# SparkFun_Soil_Moisture_Sensor.net
KiCad netlist of a schematic drawn in EAGLE
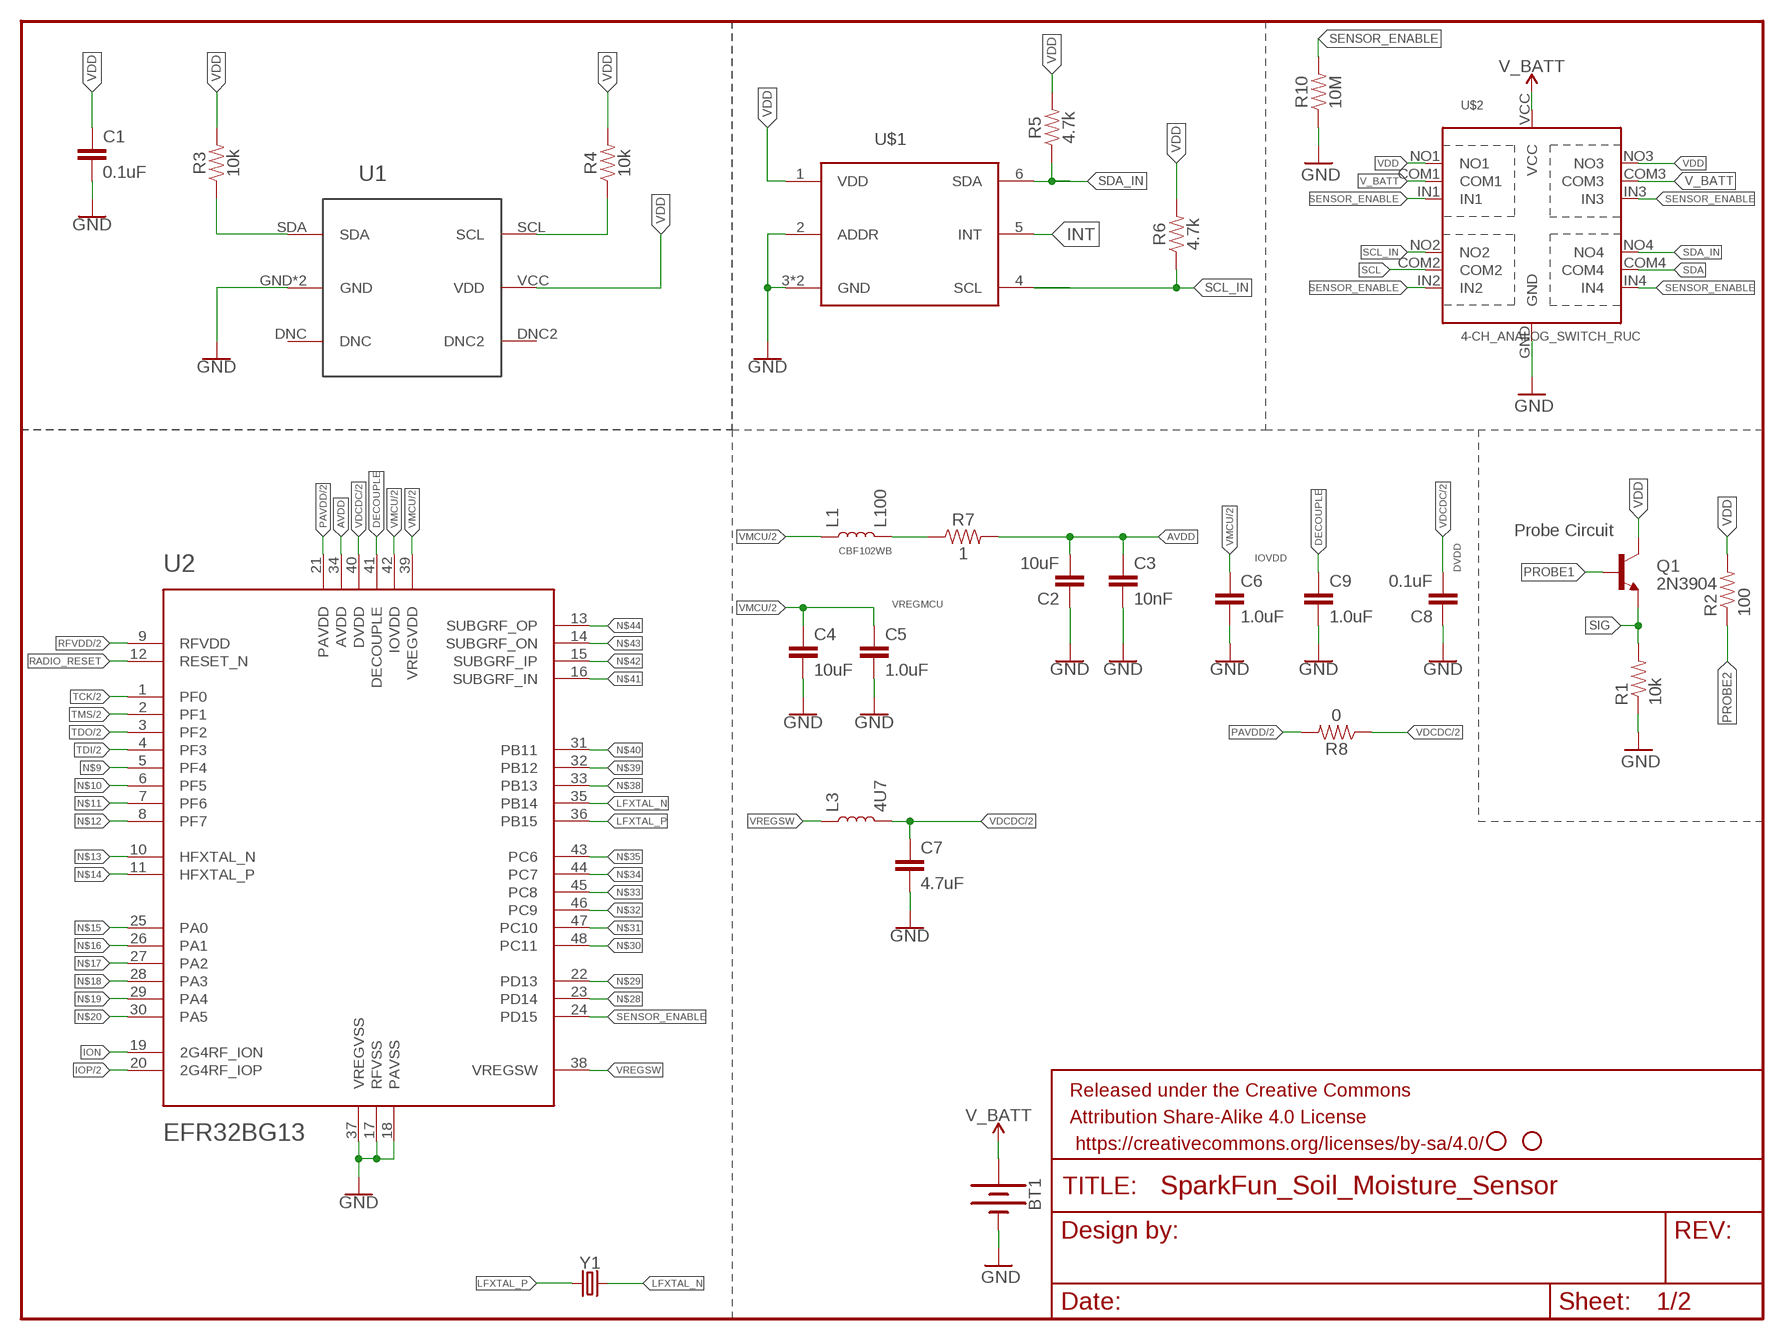
[diagram p0: schematic, sheet 1]
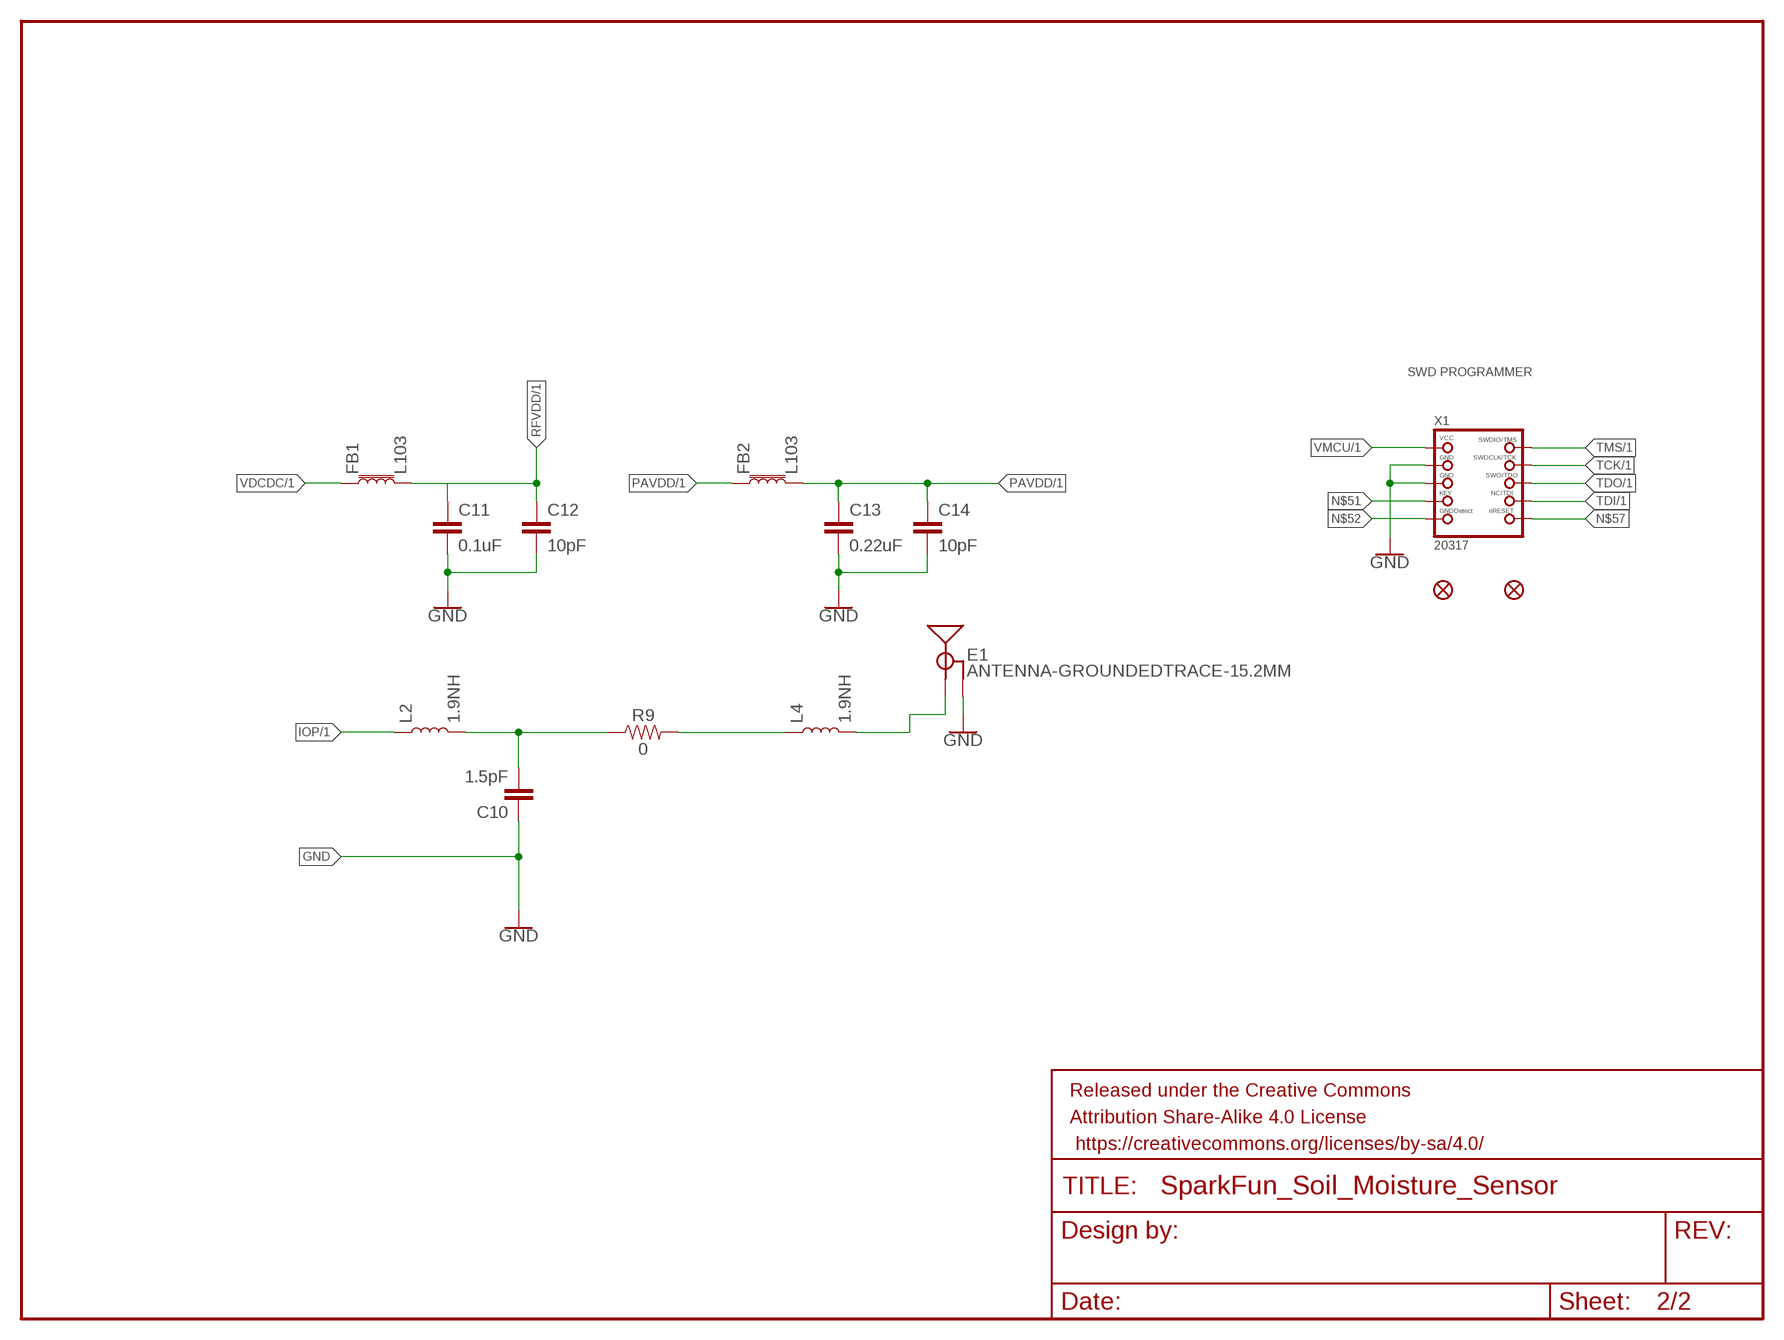
[diagram p1: schematic, sheet 2]

(export (version "E")
  (design (tool "Eeschema 10.0.6"))
  (components
    (comp (ref "BT1")
      (value "BATTERY-20MM_SMD_4LEGS_OVERPASTE")
      (footprint "eagle-import:BATTCON_20MM_4LEGS_OVERPASTE")
      (libsource (lib "eagle-import") (part "BATTERY-20MM_SMD_4LEGS_OVERPASTE"))
    )
    (comp (ref "C1")
      (value "0.1uF")
      (footprint "eagle-import:0603")
      (libsource (lib "eagle-import") (part "0.1UF-0603-25V-(+80/-20%)"))
    )
    (comp (ref "C2")
      (value "10uF")
      (footprint "eagle-import:0603")
      (libsource (lib "eagle-import") (part "10UF-0603-6.3V-20%"))
    )
    (comp (ref "C3")
      (value "10nF")
      (footprint "eagle-import:0603")
      (libsource (lib "eagle-import") (part "10NF-0603-50V-10%"))
    )
    (comp (ref "C4")
      (value "10uF")
      (footprint "eagle-import:0603")
      (libsource (lib "eagle-import") (part "10UF-0603-6.3V-20%"))
    )
    (comp (ref "C5")
      (value "1.0uF")
      (footprint "eagle-import:0603")
      (libsource (lib "eagle-import") (part "1.0UF-0603-16V-10%"))
    )
    (comp (ref "C6")
      (value "1.0uF")
      (footprint "eagle-import:0603")
      (libsource (lib "eagle-import") (part "1.0UF-0603-16V-10%"))
    )
    (comp (ref "C7")
      (value "4.7uF")
      (footprint "eagle-import:0603")
      (libsource (lib "eagle-import") (part "4.7UF0603"))
    )
    (comp (ref "C8")
      (value "0.1uF")
      (footprint "eagle-import:0603")
      (libsource (lib "eagle-import") (part "0.1UF-0603-25V-(+80/-20%)"))
    )
    (comp (ref "C9")
      (value "1.0uF")
      (footprint "eagle-import:0603")
      (libsource (lib "eagle-import") (part "1.0UF-0603-16V-10%"))
    )
    (comp (ref "FRAME1")
      (value "FRAME-LETTER")
      (footprint "eagle-import:CREATIVE_COMMONS")
      (libsource (lib "eagle-import") (part "FRAME-LETTER"))
    )
    (comp (ref "L1")
      (value "L100")
      (footprint "eagle-import:0603")
      (libsource (lib "eagle-import") (part "INDUCTOR-0603-33NH"))
    )
    (comp (ref "L3")
      (value "4U7")
      (footprint "eagle-import:1212(3030METRIC)")
      (libsource (lib "eagle-import") (part "4U7"))
    )
    (comp (ref "Q1")
      (value "2N3904")
      (footprint "eagle-import:SOT23-3")
      (libsource (lib "eagle-import") (part "TRANSISTOR_NPNMMBT2222A"))
    )
    (comp (ref "R1")
      (value "10k")
      (footprint "eagle-import:0603-RES")
      (libsource (lib "eagle-import") (part "100OHM-1/4W-5%(0603)"))
    )
    (comp (ref "R2")
      (value "100")
      (footprint "eagle-import:0603-RES")
      (libsource (lib "eagle-import") (part "100OHM-1/4W-5%(0603)"))
    )
    (comp (ref "R3")
      (value "10k")
      (footprint "eagle-import:0603")
      (libsource (lib "eagle-import") (part "10KOHM-0603-1/10W-1%"))
    )
    (comp (ref "R4")
      (value "10k")
      (footprint "eagle-import:0603")
      (libsource (lib "eagle-import") (part "10KOHM-0603-1/10W-1%"))
    )
    (comp (ref "R5")
      (value "4.7k")
      (footprint "eagle-import:0603")
      (libsource (lib "eagle-import") (part "4.7KOHM-0603-1/10W-1%"))
    )
    (comp (ref "R6")
      (value "4.7k")
      (footprint "eagle-import:0603")
      (libsource (lib "eagle-import") (part "4.7KOHM-0603-1/10W-1%"))
    )
    (comp (ref "R7")
      (value "1")
      (footprint "eagle-import:0603")
      (libsource (lib "eagle-import") (part "1OHM-0603-1/10W-1%"))
    )
    (comp (ref "R8")
      (value "0")
      (footprint "eagle-import:0603")
      (libsource (lib "eagle-import") (part "0OHM-0603-1/10W-5%"))
    )
    (comp (ref "R10")
      (value "10M")
      (footprint "eagle-import:0603")
      (libsource (lib "eagle-import") (part "10MOHM-0603-1/10W-5%"))
    )
    (comp (ref "STANDOFF1")
      (value "STAND-OFF")
      (footprint "eagle-import:STAND-OFF")
      (libsource (lib "eagle-import") (part "STAND-OFF"))
    )
    (comp (ref "STANDOFF2")
      (value "STAND-OFF")
      (footprint "eagle-import:STAND-OFF")
      (libsource (lib "eagle-import") (part "STAND-OFF"))
    )
    (comp (ref "U$1")
      (value "OPT3001DNPT")
      (footprint "eagle-import:6PIN_USON")
      (libsource (lib "eagle-import") (part "OPT3001DNPT"))
    )
    (comp (ref "U$2")
      (value "4-CH_ANALOG_SWITCH_RUC")
      (footprint "eagle-import:PX2QFN14_RUC")
      (libsource (lib "eagle-import") (part "4-CH_ANALOG_SWITCH_RUC"))
    )
    (comp (ref "U1")
      (value "SI7021_TEMP_HUMIDTY")
      (footprint "eagle-import:DFN-6")
      (libsource (lib "eagle-import") (part "SI7021_TEMP_HUMIDTY"))
    )
    (comp (ref "U2")
      (value "EFR32BG13")
      (footprint "eagle-import:QFN48")
      (libsource (lib "eagle-import") (part "EFR32BG13"))
    )
    (comp (ref "Y1")
      (value "32.768KHZ_LOW_FREQ_CRYSTAL")
      (footprint "eagle-import:CRYSTAL_1.2X0.6")
      (libsource (lib "eagle-import") (part "32.768KHZ_LOW_FREQ_CRYSTAL"))
    )
    (comp (ref "C10")
      (value "1.5pF")
      (footprint "eagle-import:0603")
      (libsource (lib "eagle-import") (part "1.5PF-0603-50V-16.667%"))
    )
    (comp (ref "C11")
      (value "0.1uF")
      (footprint "eagle-import:0603")
      (libsource (lib "eagle-import") (part "0.1UF-0603-25V-(+80/-20%)"))
    )
    (comp (ref "C12")
      (value "10pF")
      (footprint "eagle-import:0603")
      (libsource (lib "eagle-import") (part "10PF-0603-50V-5%"))
    )
    (comp (ref "C13")
      (value "0.22uF")
      (footprint "eagle-import:0603")
      (libsource (lib "eagle-import") (part "0.22UF-0603-25V-10%"))
    )
    (comp (ref "C14")
      (value "10pF")
      (footprint "eagle-import:0603")
      (libsource (lib "eagle-import") (part "10PF-0603-50V-5%"))
    )
    (comp (ref "E1")
      (value "ANTENNA-GROUNDEDTRACE-15.2MM")
      (footprint "eagle-import:TRACE_ANTENNA_2.4GHZ_15.2MM")
      (libsource (lib "eagle-import") (part "ANTENNA-GROUNDEDTRACE-15.2MM"))
    )
    (comp (ref "FB1")
      (value "L103")
      (footprint "eagle-import:0603")
      (libsource (lib "eagle-import") (part "FERRITE_BEAD-0603"))
    )
    (comp (ref "FB2")
      (value "L103")
      (footprint "eagle-import:0603")
      (libsource (lib "eagle-import") (part "FERRITE_BEAD-0603"))
    )
    (comp (ref "FID1")
      (value "FIDUCIAL\"\"")
      (footprint "eagle-import:FIDUCIAL_1MM")
      (libsource (lib "eagle-import") (part "FIDUCIAL{dblquote}{dblquote}"))
    )
    (comp (ref "FID2")
      (value "FIDUCIAL\"\"")
      (footprint "eagle-import:FIDUCIAL_1MM")
      (libsource (lib "eagle-import") (part "FIDUCIAL{dblquote}{dblquote}"))
    )
    (comp (ref "FRAME2")
      (value "FRAME-LETTER")
      (footprint "eagle-import:CREATIVE_COMMONS")
      (libsource (lib "eagle-import") (part "FRAME-LETTER"))
    )
    (comp (ref "L2")
      (value "1.9NH")
      (footprint "eagle-import:0402")
      (libsource (lib "eagle-import") (part "INDUCTOR-0402-3.9NH"))
    )
    (comp (ref "L4")
      (value "1.9NH")
      (footprint "eagle-import:0402")
      (libsource (lib "eagle-import") (part "INDUCTOR-0402-3.9NH"))
    )
    (comp (ref "R9")
      (value "0")
      (footprint "eagle-import:0805")
      (libsource (lib "eagle-import") (part "0.22OHM-0805-1/4W-1%"))
    )
    (comp (ref "X1")
      (value "20317")
      (footprint "eagle-import:2X05_1.27MM_BOX_POSTS")
      (libsource (lib "eagle-import") (part "JTAG-CORTEXBOXPOSTS"))
    )
  )
  (nets
    (net (code "1") (name "AVDD") (class "Default")
      (node (ref "C2") (pin "2") (pinfunction "2_2") (pintype "passive"))
      (node (ref "C3") (pin "1") (pinfunction "1_1") (pintype "passive"))
      (node (ref "R7") (pin "2") (pinfunction "2_2") (pintype "passive"))
      (node (ref "U2") (pin "34") (pinfunction "AVDD_34") (pintype "bidirectional"))
    )
    (net (code "2") (name "DECOUPLE") (class "Default")
      (node (ref "C9") (pin "1") (pinfunction "1_1") (pintype "passive"))
      (node (ref "U2") (pin "41") (pinfunction "DECOUPLE_41") (pintype "bidirectional"))
    )
    (net (code "3") (name "GND") (class "Default")
      (node (ref "BT1") (pin "2") (pinfunction "-_2") (pintype "power_in"))
      (node (ref "C1") (pin "2") (pinfunction "2_2") (pintype "passive"))
      (node (ref "C10") (pin "1") (pinfunction "1_1") (pintype "passive"))
      (node (ref "C11") (pin "2") (pinfunction "2_2") (pintype "passive"))
      (node (ref "C12") (pin "2") (pinfunction "2_2") (pintype "passive"))
      (node (ref "C13") (pin "2") (pinfunction "2_2") (pintype "passive"))
      (node (ref "C14") (pin "2") (pinfunction "2_2") (pintype "passive"))
      (node (ref "C2") (pin "1") (pinfunction "1_1") (pintype "passive"))
      (node (ref "C3") (pin "2") (pinfunction "2_2") (pintype "passive"))
      (node (ref "C4") (pin "2") (pinfunction "2_2") (pintype "passive"))
      (node (ref "C5") (pin "2") (pinfunction "2_2") (pintype "passive"))
      (node (ref "C6") (pin "2") (pinfunction "2_2") (pintype "passive"))
      (node (ref "C7") (pin "2") (pinfunction "2_2") (pintype "passive"))
      (node (ref "C8") (pin "1") (pinfunction "1_1") (pintype "passive"))
      (node (ref "C9") (pin "2") (pinfunction "2_2") (pintype "passive"))
      (node (ref "E1") (pin "GND") (pinfunction "GND_GND") (pintype "bidirectional"))
      (node (ref "R1") (pin "1") (pinfunction "1_1") (pintype "passive"))
      (node (ref "R10") (pin "1") (pinfunction "1_1") (pintype "passive"))
      (node (ref "U$1") (pin "2") (pinfunction "ADDR_2") (pintype "bidirectional"))
      (node (ref "U$1") (pin "3") (pinfunction "GND_3") (pintype "bidirectional"))
      (node (ref "U$1") (pin "GND") (pinfunction "GND_GND") (pintype "bidirectional"))
      (node (ref "U$2") (pin "GND") (pinfunction "GND_GND") (pintype "bidirectional"))
      (node (ref "U1") (pin "GND") (pinfunction "GND_GND") (pintype "bidirectional"))
      (node (ref "U1") (pin "GND2") (pinfunction "GND_GND2") (pintype "bidirectional"))
      (node (ref "U2") (pin "17") (pinfunction "RFVSS_17") (pintype "bidirectional"))
      (node (ref "U2") (pin "18") (pinfunction "PAVSS_18") (pintype "bidirectional"))
      (node (ref "U2") (pin "37") (pinfunction "VREGVSS_37") (pintype "bidirectional"))
      (node (ref "X1") (pin "3") (pinfunction "GND_3") (pintype "power_in"))
      (node (ref "X1") (pin "5") (pinfunction "GND_5") (pintype "power_in"))
    )
    (net (code "4") (name "INT") (class "Default")
      (node (ref "U$1") (pin "5") (pinfunction "INT_5") (pintype "bidirectional"))
    )
    (net (code "5") (name "ION") (class "Default")
      (node (ref "U2") (pin "19") (pinfunction "2G4RF_ION_19") (pintype "bidirectional"))
    )
    (net (code "6") (name "IOP") (class "Default")
      (node (ref "L2") (pin "1") (pinfunction "1_1") (pintype "passive"))
      (node (ref "U2") (pin "20") (pinfunction "2G4RF_IOP_20") (pintype "bidirectional"))
    )
    (net (code "7") (name "LFXTAL_N") (class "Default")
      (node (ref "U2") (pin "35") (pinfunction "PB14_35") (pintype "bidirectional"))
      (node (ref "Y1") (pin "P$2") (pinfunction "2_P$2") (pintype "passive"))
    )
    (net (code "8") (name "LFXTAL_P") (class "Default")
      (node (ref "U2") (pin "36") (pinfunction "PB15_36") (pintype "bidirectional"))
      (node (ref "Y1") (pin "P$1") (pinfunction "1_P$1") (pintype "passive"))
    )
    (net (code "9") (name "N$9") (class "Default")
      (node (ref "U2") (pin "5") (pinfunction "PF4_5") (pintype "bidirectional"))
    )
    (net (code "10") (name "N$10") (class "Default")
      (node (ref "U2") (pin "6") (pinfunction "PF5_6") (pintype "bidirectional"))
    )
    (net (code "11") (name "N$11") (class "Default")
      (node (ref "U2") (pin "7") (pinfunction "PF6_7") (pintype "bidirectional"))
    )
    (net (code "12") (name "N$12") (class "Default")
      (node (ref "U2") (pin "8") (pinfunction "PF7_8") (pintype "bidirectional"))
    )
    (net (code "13") (name "N$13") (class "Default")
      (node (ref "U2") (pin "10") (pinfunction "HFXTAL_N_10") (pintype "bidirectional"))
    )
    (net (code "14") (name "N$14") (class "Default")
      (node (ref "U2") (pin "11") (pinfunction "HFXTAL_P_11") (pintype "bidirectional"))
    )
    (net (code "15") (name "N$15") (class "Default")
      (node (ref "U2") (pin "25") (pinfunction "PA0_25") (pintype "bidirectional"))
    )
    (net (code "16") (name "N$16") (class "Default")
      (node (ref "U2") (pin "26") (pinfunction "PA1_26") (pintype "bidirectional"))
    )
    (net (code "17") (name "N$17") (class "Default")
      (node (ref "U2") (pin "27") (pinfunction "PA2_27") (pintype "bidirectional"))
    )
    (net (code "18") (name "N$18") (class "Default")
      (node (ref "U2") (pin "28") (pinfunction "PA3_28") (pintype "bidirectional"))
    )
    (net (code "19") (name "N$19") (class "Default")
      (node (ref "U2") (pin "29") (pinfunction "PA4_29") (pintype "bidirectional"))
    )
    (net (code "20") (name "N$20") (class "Default")
      (node (ref "U2") (pin "30") (pinfunction "PA5_30") (pintype "bidirectional"))
    )
    (net (code "21") (name "N$28") (class "Default")
      (node (ref "U2") (pin "23") (pinfunction "PD14_23") (pintype "bidirectional"))
    )
    (net (code "22") (name "N$29") (class "Default")
      (node (ref "U2") (pin "22") (pinfunction "PD13_22") (pintype "bidirectional"))
    )
    (net (code "23") (name "N$30") (class "Default")
      (node (ref "U2") (pin "48") (pinfunction "PC11_48") (pintype "bidirectional"))
    )
    (net (code "24") (name "N$31") (class "Default")
      (node (ref "U2") (pin "47") (pinfunction "PC10_47") (pintype "bidirectional"))
    )
    (net (code "25") (name "N$32") (class "Default")
      (node (ref "U2") (pin "46") (pinfunction "PC9_46") (pintype "bidirectional"))
    )
    (net (code "26") (name "N$33") (class "Default")
      (node (ref "U2") (pin "45") (pinfunction "PC8_45") (pintype "bidirectional"))
    )
    (net (code "27") (name "N$34") (class "Default")
      (node (ref "U2") (pin "44") (pinfunction "PC7_44") (pintype "bidirectional"))
    )
    (net (code "28") (name "N$35") (class "Default")
      (node (ref "U2") (pin "43") (pinfunction "PC6_43") (pintype "bidirectional"))
    )
    (net (code "29") (name "N$38") (class "Default")
      (node (ref "U2") (pin "33") (pinfunction "PB13_33") (pintype "bidirectional"))
    )
    (net (code "30") (name "N$39") (class "Default")
      (node (ref "U2") (pin "32") (pinfunction "PB12_32") (pintype "bidirectional"))
    )
    (net (code "31") (name "N$40") (class "Default")
      (node (ref "U2") (pin "31") (pinfunction "PB11_31") (pintype "bidirectional"))
    )
    (net (code "32") (name "N$41") (class "Default")
      (node (ref "U2") (pin "16") (pinfunction "SUBGRF_IN_16") (pintype "bidirectional"))
    )
    (net (code "33") (name "N$42") (class "Default")
      (node (ref "U2") (pin "15") (pinfunction "SUBGRF_IP_15") (pintype "bidirectional"))
    )
    (net (code "34") (name "N$43") (class "Default")
      (node (ref "U2") (pin "14") (pinfunction "SUBGRF_ON_14") (pintype "bidirectional"))
    )
    (net (code "35") (name "N$44") (class "Default")
      (node (ref "U2") (pin "13") (pinfunction "SUBGRF_OP_13") (pintype "bidirectional"))
    )
    (net (code "36") (name "N$51") (class "Default")
      (node (ref "X1") (pin "7") (pinfunction "KEY_7") (pintype "bidirectional"))
    )
    (net (code "37") (name "N$52") (class "Default")
      (node (ref "X1") (pin "9") (pinfunction "GNDDETECT_9") (pintype "bidirectional"))
    )
    (net (code "38") (name "N$57") (class "Default")
      (node (ref "X1") (pin "10") (pinfunction "NRESET_10") (pintype "bidirectional"))
    )
    (net (code "39") (name "Net-(C10-Pad2)") (class "Default")
      (node (ref "C10") (pin "2") (pinfunction "2_2") (pintype "passive"))
      (node (ref "L2") (pin "2") (pinfunction "2_2") (pintype "passive"))
      (node (ref "R9") (pin "1") (pinfunction "1_1") (pintype "passive"))
    )
    (net (code "40") (name "Net-(E1-SIGNAL)") (class "Default")
      (node (ref "E1") (pin "ANT") (pinfunction "SIGNAL_ANT") (pintype "bidirectional"))
      (node (ref "L4") (pin "2") (pinfunction "2_2") (pintype "passive"))
    )
    (net (code "41") (name "Net-(L1-Pad2)") (class "Default")
      (node (ref "L1") (pin "2") (pinfunction "2_2") (pintype "passive"))
      (node (ref "R7") (pin "1") (pinfunction "1_1") (pintype "passive"))
    )
    (net (code "42") (name "Net-(L4-Pad1)") (class "Default")
      (node (ref "L4") (pin "1") (pinfunction "1_1") (pintype "passive"))
      (node (ref "R9") (pin "2") (pinfunction "2_2") (pintype "passive"))
    )
    (net (code "43") (name "Net-(R3-Pad1)") (class "Default")
      (node (ref "R3") (pin "1") (pinfunction "1_1") (pintype "passive"))
      (node (ref "U1") (pin "SDA") (pinfunction "SDA_SDA") (pintype "bidirectional"))
    )
    (net (code "44") (name "Net-(R4-Pad1)") (class "Default")
      (node (ref "R4") (pin "1") (pinfunction "1_1") (pintype "passive"))
      (node (ref "U1") (pin "SCL") (pinfunction "SCL_SCL") (pintype "bidirectional"))
    )
    (net (code "45") (name "PAVDD") (class "Default")
      (node (ref "C13") (pin "1") (pinfunction "1_1") (pintype "passive"))
      (node (ref "C14") (pin "1") (pinfunction "1_1") (pintype "passive"))
      (node (ref "FB2") (pin "1") (pinfunction "1_1") (pintype "passive"))
      (node (ref "FB2") (pin "2") (pinfunction "2_2") (pintype "passive"))
      (node (ref "R8") (pin "2") (pinfunction "2_2") (pintype "passive"))
      (node (ref "U2") (pin "21") (pinfunction "PAVDD_21") (pintype "bidirectional"))
    )
    (net (code "46") (name "PROBE1") (class "Default")
      (node (ref "Q1") (pin "1") (pinfunction "B_1") (pintype "passive"))
    )
    (net (code "47") (name "PROBE2") (class "Default")
      (node (ref "R2") (pin "1") (pinfunction "1_1") (pintype "passive"))
    )
    (net (code "48") (name "RADIO_RESET") (class "Default")
      (node (ref "U2") (pin "12") (pinfunction "RESET_N_12") (pintype "bidirectional"))
    )
    (net (code "49") (name "RFVDD") (class "Default")
      (node (ref "C11") (pin "1") (pinfunction "1_1") (pintype "passive"))
      (node (ref "C12") (pin "1") (pinfunction "1_1") (pintype "passive"))
      (node (ref "FB1") (pin "2") (pinfunction "2_2") (pintype "passive"))
      (node (ref "U2") (pin "9") (pinfunction "RFVDD_9") (pintype "bidirectional"))
    )
    (net (code "50") (name "SCL") (class "Default")
      (node (ref "U$2") (pin "COM2") (pinfunction "COM2_COM2") (pintype "bidirectional"))
    )
    (net (code "51") (name "SCL_IN") (class "Default")
      (node (ref "R6") (pin "1") (pinfunction "1_1") (pintype "passive"))
      (node (ref "U$1") (pin "4") (pinfunction "SCL_4") (pintype "bidirectional"))
      (node (ref "U$2") (pin "NO2") (pinfunction "NO2_NO2") (pintype "bidirectional"))
    )
    (net (code "52") (name "SDA") (class "Default")
      (node (ref "U$2") (pin "COM4") (pinfunction "COM4_COM4") (pintype "bidirectional"))
    )
    (net (code "53") (name "SDA_IN") (class "Default")
      (node (ref "R5") (pin "1") (pinfunction "1_1") (pintype "passive"))
      (node (ref "U$1") (pin "6") (pinfunction "SDA_6") (pintype "bidirectional"))
      (node (ref "U$2") (pin "NO4") (pinfunction "NO4_NO4") (pintype "bidirectional"))
    )
    (net (code "54") (name "SENSOR_ENABLE") (class "Default")
      (node (ref "R10") (pin "2") (pinfunction "2_2") (pintype "passive"))
      (node (ref "U$2") (pin "IN1") (pinfunction "IN1_IN1") (pintype "bidirectional"))
      (node (ref "U$2") (pin "IN2") (pinfunction "IN2_IN2") (pintype "bidirectional"))
      (node (ref "U$2") (pin "IN3") (pinfunction "IN3_IN3") (pintype "bidirectional"))
      (node (ref "U$2") (pin "IN4") (pinfunction "IN4_IN4") (pintype "bidirectional"))
      (node (ref "U2") (pin "24") (pinfunction "PD15_24") (pintype "bidirectional"))
    )
    (net (code "55") (name "SIG") (class "Default")
      (node (ref "Q1") (pin "2") (pinfunction "E_2") (pintype "passive"))
      (node (ref "R1") (pin "2") (pinfunction "2_2") (pintype "passive"))
    )
    (net (code "56") (name "TCK") (class "Default")
      (node (ref "U2") (pin "1") (pinfunction "PF0_1") (pintype "bidirectional"))
      (node (ref "X1") (pin "4") (pinfunction "SWDCLK_4") (pintype "bidirectional"))
    )
    (net (code "57") (name "TDI") (class "Default")
      (node (ref "U2") (pin "4") (pinfunction "PF3_4") (pintype "bidirectional"))
      (node (ref "X1") (pin "8") (pinfunction "TDI_8") (pintype "bidirectional"))
    )
    (net (code "58") (name "TDO") (class "Default")
      (node (ref "U2") (pin "3") (pinfunction "PF2_3") (pintype "bidirectional"))
      (node (ref "X1") (pin "6") (pinfunction "SWO_6") (pintype "bidirectional"))
    )
    (net (code "59") (name "TMS") (class "Default")
      (node (ref "U2") (pin "2") (pinfunction "PF1_2") (pintype "bidirectional"))
      (node (ref "X1") (pin "2") (pinfunction "SWDIO_2") (pintype "bidirectional"))
    )
    (net (code "60") (name "VDCDC") (class "Default")
      (node (ref "C7") (pin "1") (pinfunction "1_1") (pintype "passive"))
      (node (ref "C8") (pin "2") (pinfunction "2_2") (pintype "passive"))
      (node (ref "FB1") (pin "1") (pinfunction "1_1") (pintype "passive"))
      (node (ref "L3") (pin "P$2") (pinfunction "2_P$2") (pintype "passive"))
      (node (ref "R8") (pin "1") (pinfunction "1_1") (pintype "passive"))
      (node (ref "U2") (pin "40") (pinfunction "DVDD_40") (pintype "bidirectional"))
    )
    (net (code "61") (name "VDD") (class "Default")
      (node (ref "C1") (pin "1") (pinfunction "1_1") (pintype "passive"))
      (node (ref "Q1") (pin "3") (pinfunction "C_3") (pintype "passive"))
      (node (ref "R2") (pin "2") (pinfunction "2_2") (pintype "passive"))
      (node (ref "R3") (pin "2") (pinfunction "2_2") (pintype "passive"))
      (node (ref "R4") (pin "2") (pinfunction "2_2") (pintype "passive"))
      (node (ref "R5") (pin "2") (pinfunction "2_2") (pintype "passive"))
      (node (ref "R6") (pin "2") (pinfunction "2_2") (pintype "passive"))
      (node (ref "U$1") (pin "1") (pinfunction "VDD_1") (pintype "bidirectional"))
      (node (ref "U$2") (pin "NO1") (pinfunction "NO1_NO1") (pintype "bidirectional"))
      (node (ref "U$2") (pin "NO3") (pinfunction "NO3_NO3") (pintype "bidirectional"))
      (node (ref "U1") (pin "VCC") (pinfunction "VDD_VCC") (pintype "bidirectional"))
    )
    (net (code "62") (name "VMCU") (class "Default")
      (node (ref "C4") (pin "1") (pinfunction "1_1") (pintype "passive"))
      (node (ref "C5") (pin "1") (pinfunction "1_1") (pintype "passive"))
      (node (ref "C6") (pin "1") (pinfunction "1_1") (pintype "passive"))
      (node (ref "L1") (pin "1") (pinfunction "1_1") (pintype "passive"))
      (node (ref "U2") (pin "39") (pinfunction "VREGVDD_39") (pintype "bidirectional"))
      (node (ref "U2") (pin "42") (pinfunction "IOVDD_42") (pintype "bidirectional"))
      (node (ref "X1") (pin "1") (pinfunction "VCC_1") (pintype "power_in"))
    )
    (net (code "63") (name "VREGSW") (class "Default")
      (node (ref "L3") (pin "P$1") (pinfunction "1_P$1") (pintype "passive"))
      (node (ref "U2") (pin "38") (pinfunction "VREGSW_38") (pintype "bidirectional"))
    )
    (net (code "64") (name "V_BATT") (class "Default")
      (node (ref "BT1") (pin "1") (pinfunction "+_1") (pintype "power_in"))
      (node (ref "U$2") (pin "COM1") (pinfunction "COM1_COM1") (pintype "bidirectional"))
      (node (ref "U$2") (pin "COM3") (pinfunction "COM3_COM3") (pintype "bidirectional"))
      (node (ref "U$2") (pin "VCC") (pinfunction "VCC_VCC") (pintype "bidirectional"))
    )
    (net (code "65") (name "unconnected-(U1-PadDNC)") (class "Default")
      (node (ref "U1") (pin "DNC") (pinfunction "DNC_DNC") (pintype "bidirectional"))
    )
    (net (code "66") (name "unconnected-(U1-PadDNC2)") (class "Default")
      (node (ref "U1") (pin "DNC2") (pinfunction "DNC2_DNC2") (pintype "bidirectional"))
    )
  )
)
